# AIRZAI_LED_SENSE_FLEX_REVC.net
KiCad netlist of a schematic drawn in Altium Designer
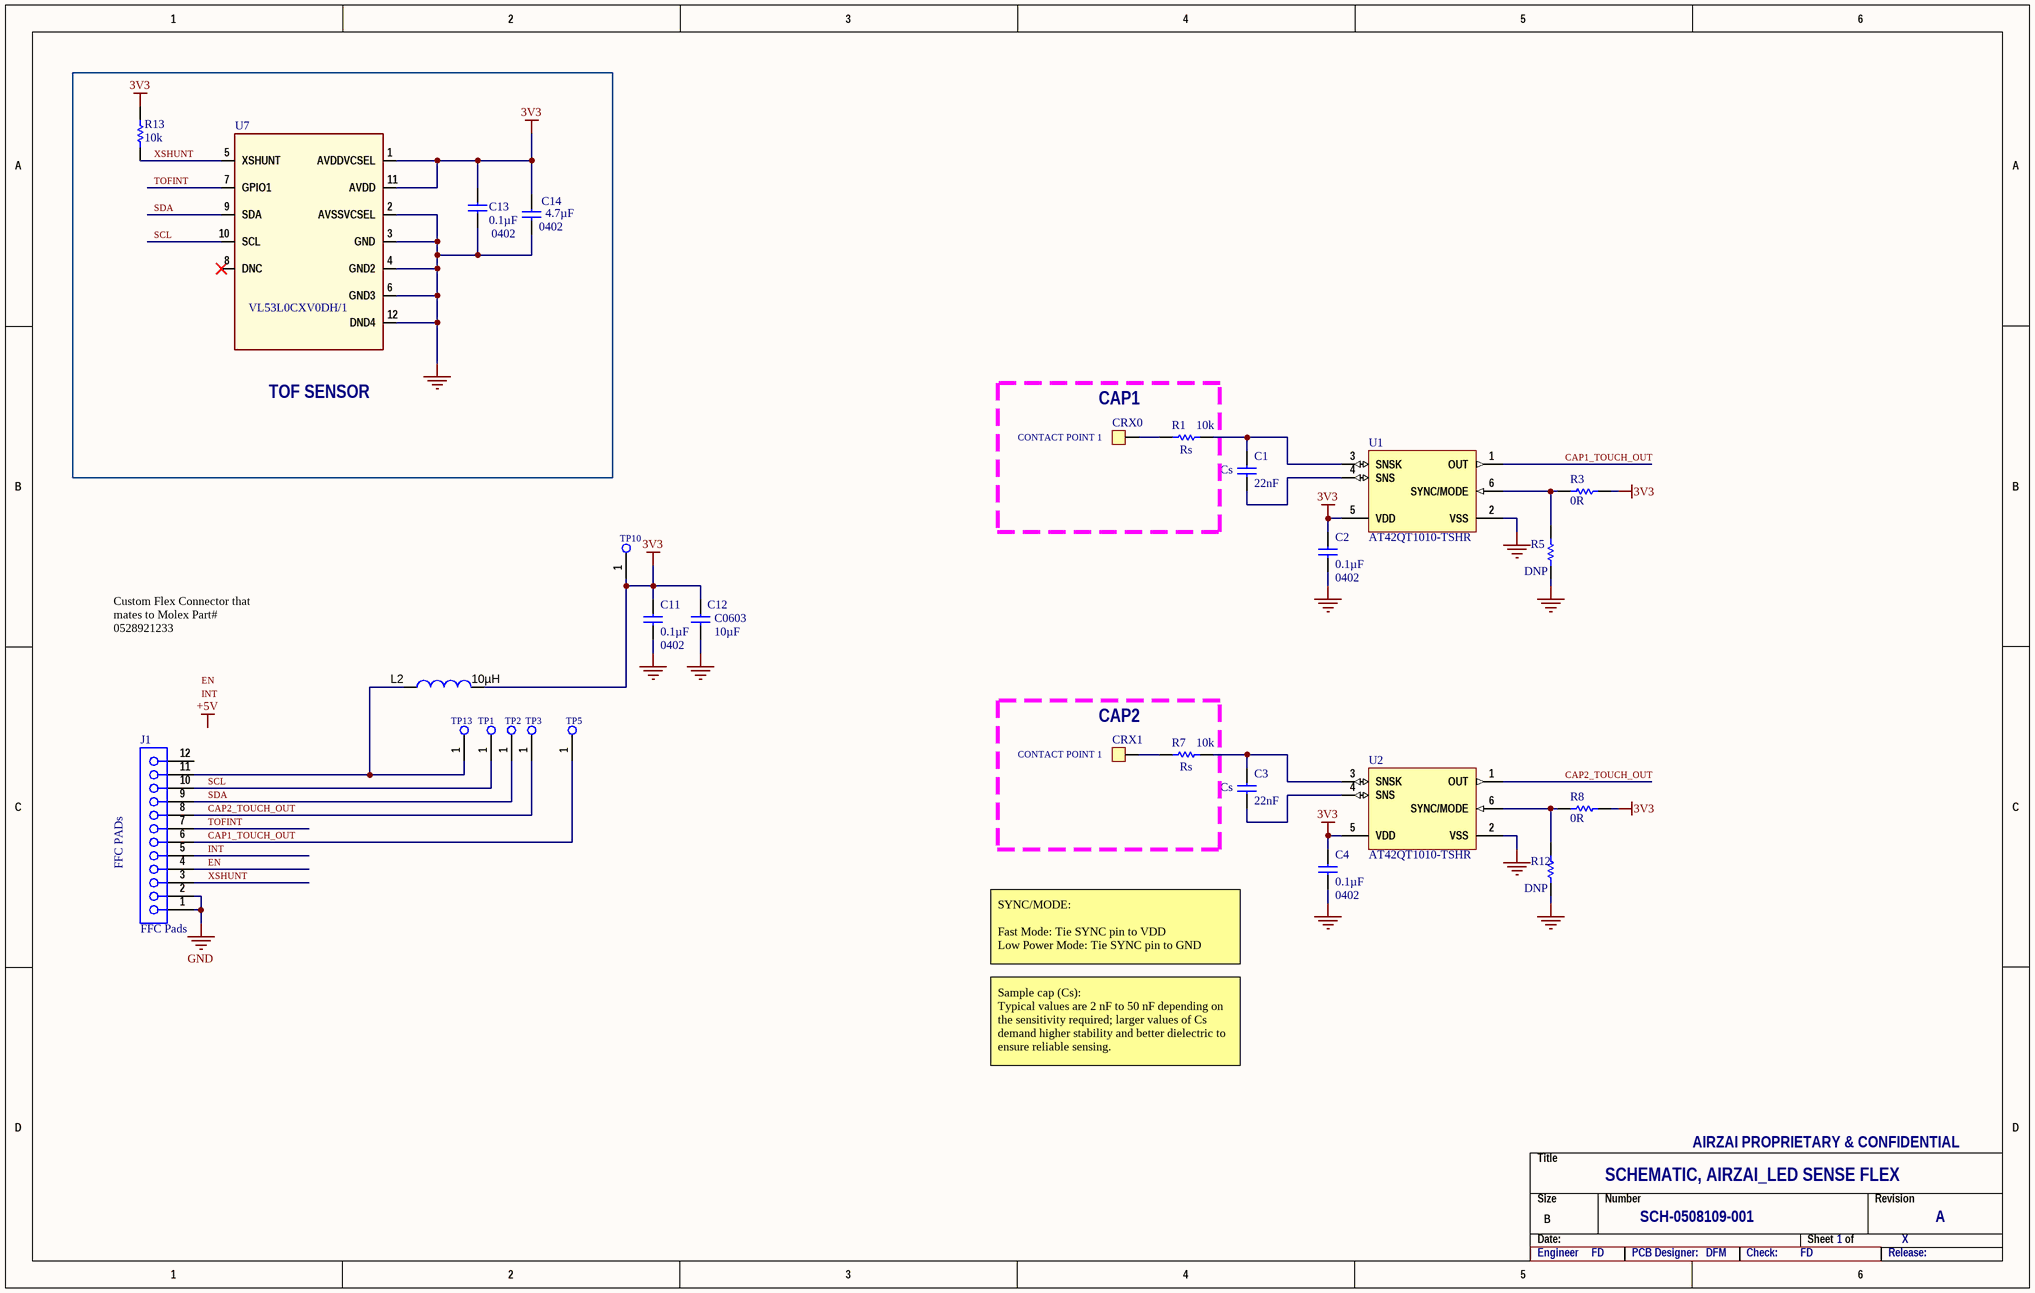
[diagram p0: AIRZAI_LED_SENSE_FLEX_REVC.SchDoc]

(export (version "E")
  (design (tool "Eeschema 10.0.6"))
  (components
    (comp (ref "C1")
      (value "22nF")
      (footprint "0402CAP")
      (description "Capacitor, X7R, ±10%")
      (fields
        (field (name "MANUFACTURER") "TDK")
        (field (name "MANUFACTURER PART NUMBER") "CGA2B2X7R1E223K050BA")
      )
      (libsource (lib "Nordic Passive DB") (part "CAP"))
    )
    (comp (ref "C2")
      (value "0.1µF")
      (footprint "0402")
      (description "Capacitor, X7R, ±10%")
      (fields (field (name "MANUFACTURER") "TDK") (field (name "MANUFACTURER PART NUMBER") "C1005X7R1C104K"))
      (libsource (lib "Nordic Passive DB") (part "CAP"))
    )
    (comp (ref "C3")
      (value "22nF")
      (footprint "0402CAP")
      (description "Capacitor, X7R, ±10%")
      (fields
        (field (name "MANUFACTURER") "TDK")
        (field (name "MANUFACTURER PART NUMBER") "CGA2B2X7R1E223K050BA")
      )
      (libsource (lib "Nordic Passive DB") (part "CAP"))
    )
    (comp (ref "C4")
      (value "0.1µF")
      (footprint "0402")
      (description "Capacitor, X7R, ±10%")
      (fields (field (name "MANUFACTURER") "TDK") (field (name "MANUFACTURER PART NUMBER") "C1005X7R1C104K"))
      (libsource (lib "Nordic Passive DB") (part "CAP"))
    )
    (comp (ref "C11")
      (value "0.1µF")
      (footprint "0402")
      (description "Capacitor, X7R, ±10%")
      (fields (field (name "MANUFACTURER") "TDK") (field (name "MANUFACTURER PART NUMBER") "C1005X7R1C104K"))
      (libsource (lib "Nordic Passive DB") (part "CAP"))
    )
    (comp (ref "C12")
      (value "10µF")
      (footprint "C0603")
      (description "Capacitor, X7R, ±10%")
      (fields
        (field (name "MANUFACTURER") "MURATA")
        (field (name "MANUFACTURER PART NUMBER") "GRM188R60J106ME47D")
      )
      (libsource (lib "Nordic Passive DB") (part "CAP"))
    )
    (comp (ref "C13")
      (value "0.1µF")
      (footprint "0402")
      (description "Capacitor, X7R, ±10%")
      (fields (field (name "MANUFACTURER") "TDK") (field (name "MANUFACTURER PART NUMBER") "C1005X7R1C104K"))
      (libsource (lib "Nordic Passive DB") (part "CAP"))
    )
    (comp (ref "C14")
      (value "4.7µF")
      (footprint "0402")
      (description "Capacitor, X7R, ±10%")
      (fields (field (name "MANUFACTURER") "TDK") (field (name "MANUFACTURER PART NUMBER") "C1005X5R0J475M"))
      (libsource (lib "Nordic Passive DB") (part "CAP"))
    )
    (comp (ref "CRX0")
      (value "CONTACT POINT 1")
      (footprint "CONTACT_POINT_1CM _SQ")
      (libsource (lib "AIRZAI_LED_SENSE_FLEX_REVA") (part "WIRE_POINT"))
    )
    (comp (ref "CRX1")
      (value "CONTACT POINT 1")
      (footprint "CONTACT_POINT_1CM _SQ")
      (libsource (lib "AIRZAI_LED_SENSE_FLEX_REVA") (part "WIRE_POINT"))
    )
    (comp (ref "J1")
      (value "FFC Pads")
      (footprint "FFC_Pads")
      (description "0.5 mm Pitch FFC Pads")
      (libsource (lib "AIRZAI_LED_SENSE_FLEX_REVA") (part "FFC_PADS"))
    )
    (comp (ref "L2")
      (value "CB2012T100KR")
      (footprint "0805")
      (description "Inductor, 10 µH, 0.5A, 0.65 ohm, SMD")
      (fields
        (field (name "MANUFACTURER") "Taiyo Yuden")
        (field (name "TOLERANCE") "10%")
        (field (name "VALUEDISPLAYED") "10µH")
      )
      (libsource (lib "AIRZAI_LED_SENSE_FLEX_REVA") (part "CB2012T100KR"))
    )
    (comp (ref "R1")
      (value "10k")
      (footprint "0402")
      (description "10k 0.063W 1% 0402 (1005 Metric)  SMD")
      (fields (field (name "TOLERANCE") "None") (field (name "POWER") "0.063W"))
      (libsource (lib "AIRZAI_LED_SENSE_FLEX_REVA") (part "RES"))
    )
    (comp (ref "R3")
      (value "0R")
      (footprint "0402")
      (description "Jumper 0402 (1005 Metric)")
      (fields (field (name "TOLERANCE") "None") (field (name "MANUFACTURER") "Panasonic"))
      (libsource (lib "AIRZAI_LED_SENSE_FLEX_REVA") (part "RES"))
    )
    (comp (ref "R5")
      (value "DNP")
      (footprint "0402")
      (fields
        (field (name "TOLERANCE") "None")
        (field (name "POWER") "0.0625 W")
        (field (name "Comment") "DNP 0402(1005)")
      )
      (libsource (lib "AIRZAI_LED_SENSE_FLEX_REVA") (part "RES"))
    )
    (comp (ref "R7")
      (value "10k")
      (footprint "0402")
      (description "10k 0.063W 1% 0402 (1005 Metric)  SMD")
      (fields (field (name "TOLERANCE") "None") (field (name "POWER") "0.063W"))
      (libsource (lib "AIRZAI_LED_SENSE_FLEX_REVA") (part "RES"))
    )
    (comp (ref "R8")
      (value "0R")
      (footprint "0402")
      (description "Jumper 0402 (1005 Metric)")
      (fields (field (name "TOLERANCE") "None") (field (name "MANUFACTURER") "Panasonic"))
      (libsource (lib "AIRZAI_LED_SENSE_FLEX_REVA") (part "RES"))
    )
    (comp (ref "R12")
      (value "DNP")
      (footprint "0402")
      (fields
        (field (name "TOLERANCE") "None")
        (field (name "POWER") "0.0625 W")
        (field (name "Comment") "DNP 0402(1005)")
      )
      (libsource (lib "AIRZAI_LED_SENSE_FLEX_REVA") (part "RES"))
    )
    (comp (ref "R13")
      (value "10k")
      (footprint "0402")
      (description "10k 0.063W 1% 0402 (1005 Metric)  SMD")
      (fields (field (name "TOLERANCE") "None") (field (name "POWER") "0.063W"))
      (libsource (lib "AIRZAI_LED_SENSE_FLEX_REVA") (part "RES"))
    )
    (comp (ref "TP1")
      (value "Test Point")
      (footprint "TP_0.9MM")
      (libsource (lib "AIRZAI_LED_SENSE_FLEX_REVA") (part "Test Point"))
    )
    (comp (ref "TP2")
      (value "Test Point")
      (footprint "TP_0.9MM")
      (libsource (lib "AIRZAI_LED_SENSE_FLEX_REVA") (part "Test Point"))
    )
    (comp (ref "TP3")
      (value "Test Point")
      (footprint "TP_0.9MM")
      (libsource (lib "AIRZAI_LED_SENSE_FLEX_REVA") (part "Test Point"))
    )
    (comp (ref "TP5")
      (value "Test Point")
      (footprint "TP_0.9MM")
      (libsource (lib "AIRZAI_LED_SENSE_FLEX_REVA") (part "Test Point"))
    )
    (comp (ref "TP10")
      (value "Test Point")
      (footprint "TP_0.9MM")
      (libsource (lib "AIRZAI_LED_SENSE_FLEX_REVA") (part "Test Point"))
    )
    (comp (ref "TP13")
      (value "Test Point")
      (footprint "TP_0.9MM")
      (libsource (lib "AIRZAI_LED_SENSE_FLEX_REVA") (part "Test Point"))
    )
    (comp (ref "U1")
      (value "AT42QT1010-TSHR")
      (footprint "SOT-23-6-AT42QT1010-TSHR")
      (description "One-channel Touch Sensor IC with Reset Timer, -40° to +85° C, 6-pin SOT23")
      (libsource (lib "AIRZAI_LED_SENSE_FLEX_REVA") (part "AT42QT1010-TSHR"))
    )
    (comp (ref "U2")
      (value "AT42QT1010-TSHR")
      (footprint "SOT-23-6-AT42QT1010-TSHR")
      (description "One-channel Touch Sensor IC with Reset Timer, -40° to +85° C, 6-pin SOT23")
      (libsource (lib "AIRZAI_LED_SENSE_FLEX_REVA") (part "AT42QT1010-TSHR"))
    )
    (comp (ref "U7")
      (value "VL53L0CXV0DH/1")
      (footprint "VL53L0X")
      (fields (field (name "MANUFACTURER") "ST") (field (name "TOLERANCE") "None"))
      (libsource (lib "DFM_JBKEGSVS_Library") (part "VL53L0X"))
    )
  )
  (nets
    (net (code "2") (name "/CAP1_TOUCH_OUT") (class "Default")
      (node (ref "J1") (pin "6") (pinfunction "6_6") (pintype "passive"))
      (node (ref "TP5") (pin "1") (pinfunction "1_1") (pintype "passive"))
      (node (ref "U1") (pin "1") (pinfunction "OUT_1") (pintype "output"))
    )
    (net (code "3") (name "/CAP2_TOUCH_OUT") (class "Default")
      (node (ref "J1") (pin "8") (pinfunction "8_8") (pintype "passive"))
      (node (ref "TP3") (pin "1") (pinfunction "1_1") (pintype "passive"))
      (node (ref "U2") (pin "1") (pinfunction "OUT_1") (pintype "output"))
    )
    (net (code "4") (name "/EN") (class "Default")
      (node (ref "J1") (pin "4") (pinfunction "4_4") (pintype "passive"))
    )
    (net (code "5") (name "/INT") (class "Default")
      (node (ref "J1") (pin "5") (pinfunction "5_5") (pintype "passive"))
    )
    (net (code "6") (name "/SCL") (class "Default")
      (node (ref "J1") (pin "10") (pinfunction "10_10") (pintype "passive"))
      (node (ref "TP1") (pin "1") (pinfunction "1_1") (pintype "passive"))
      (node (ref "U7") (pin "10") (pinfunction "SCL_10") (pintype "passive"))
    )
    (net (code "7") (name "/SDA") (class "Default")
      (node (ref "J1") (pin "9") (pinfunction "9_9") (pintype "passive"))
      (node (ref "TP2") (pin "1") (pinfunction "1_1") (pintype "passive"))
      (node (ref "U7") (pin "9") (pinfunction "SDA_9") (pintype "passive"))
    )
    (net (code "8") (name "/TOFINT") (class "Default")
      (node (ref "J1") (pin "7") (pinfunction "7_7") (pintype "passive"))
      (node (ref "U7") (pin "7") (pinfunction "GPIO1_7") (pintype "passive"))
    )
    (net (code "9") (name "/XSHUNT") (class "Default")
      (node (ref "J1") (pin "3") (pinfunction "3_3") (pintype "passive"))
      (node (ref "R13") (pin "2") (pinfunction "2_2") (pintype "passive"))
      (node (ref "U7") (pin "5") (pinfunction "XSHUNT_5") (pintype "passive"))
    )
    (net (code "10") (name "3V3") (class "Default")
      (node (ref "C11") (pin "1") (pinfunction "1_1") (pintype "passive"))
      (node (ref "C12") (pin "1") (pinfunction "1_1") (pintype "passive"))
      (node (ref "C13") (pin "1") (pinfunction "1_1") (pintype "passive"))
      (node (ref "C14") (pin "2") (pinfunction "2_2") (pintype "passive"))
      (node (ref "C2") (pin "1") (pinfunction "1_1") (pintype "passive"))
      (node (ref "C4") (pin "1") (pinfunction "1_1") (pintype "passive"))
      (node (ref "L2") (pin "2") (pinfunction "2_2") (pintype "passive"))
      (node (ref "R13") (pin "1") (pinfunction "1_1") (pintype "passive"))
      (node (ref "R3") (pin "2") (pinfunction "2_2") (pintype "passive"))
      (node (ref "R8") (pin "2") (pinfunction "2_2") (pintype "passive"))
      (node (ref "TP10") (pin "1") (pinfunction "1_1") (pintype "passive"))
      (node (ref "U1") (pin "5") (pinfunction "VDD_5") (pintype "power_in"))
      (node (ref "U2") (pin "5") (pinfunction "VDD_5") (pintype "power_in"))
      (node (ref "U7") (pin "1") (pinfunction "AVDDVCSEL_1") (pintype "passive"))
      (node (ref "U7") (pin "11") (pinfunction "AVDD_11") (pintype "passive"))
    )
    (net (code "11") (name "GND") (class "Default")
      (node (ref "C11") (pin "2") (pinfunction "2_2") (pintype "passive"))
      (node (ref "C12") (pin "2") (pinfunction "2_2") (pintype "passive"))
      (node (ref "C13") (pin "2") (pinfunction "2_2") (pintype "passive"))
      (node (ref "C14") (pin "1") (pinfunction "1_1") (pintype "passive"))
      (node (ref "C2") (pin "2") (pinfunction "2_2") (pintype "passive"))
      (node (ref "C4") (pin "2") (pinfunction "2_2") (pintype "passive"))
      (node (ref "J1") (pin "1") (pinfunction "1_1") (pintype "passive"))
      (node (ref "J1") (pin "2") (pinfunction "2_2") (pintype "passive"))
      (node (ref "R12") (pin "2") (pinfunction "2_2") (pintype "passive"))
      (node (ref "R5") (pin "2") (pinfunction "2_2") (pintype "passive"))
      (node (ref "U1") (pin "2") (pinfunction "VSS_2") (pintype "power_in"))
      (node (ref "U2") (pin "2") (pinfunction "VSS_2") (pintype "power_in"))
      (node (ref "U7") (pin "12") (pinfunction "DND4_12") (pintype "passive"))
      (node (ref "U7") (pin "2") (pinfunction "AVSSVCSEL_2") (pintype "passive"))
      (node (ref "U7") (pin "3") (pinfunction "GND_3") (pintype "passive"))
      (node (ref "U7") (pin "4") (pinfunction "GND2_4") (pintype "passive"))
      (node (ref "U7") (pin "6") (pinfunction "GND3_6") (pintype "passive"))
    )
    (net (code "12") (name "Net-(CRX0-Pad1)") (class "Default")
      (node (ref "CRX0") (pin "1") (pinfunction "1_1") (pintype "passive"))
      (node (ref "R1") (pin "2") (pinfunction "2_2") (pintype "passive"))
    )
    (net (code "13") (name "Net-(CRX1-Pad1)") (class "Default")
      (node (ref "CRX1") (pin "1") (pinfunction "1_1") (pintype "passive"))
      (node (ref "R7") (pin "2") (pinfunction "2_2") (pintype "passive"))
    )
    (net (code "14") (name "Net-(J1-Pad11)") (class "Default")
      (node (ref "J1") (pin "11") (pinfunction "11_11") (pintype "passive"))
      (node (ref "L2") (pin "1") (pinfunction "1_1") (pintype "passive"))
      (node (ref "TP13") (pin "1") (pinfunction "1_1") (pintype "passive"))
    )
    (net (code "15") (name "Net-(U1-SNS)") (class "Default")
      (node (ref "C1") (pin "2") (pinfunction "2_2") (pintype "passive"))
      (node (ref "U1") (pin "4") (pinfunction "SNS_4") (pintype "bidirectional"))
    )
    (net (code "16") (name "Net-(U1-SNSK)") (class "Default")
      (node (ref "C1") (pin "1") (pinfunction "1_1") (pintype "passive"))
      (node (ref "R1") (pin "1") (pinfunction "1_1") (pintype "passive"))
      (node (ref "U1") (pin "3") (pinfunction "SNSK_3") (pintype "bidirectional"))
    )
    (net (code "17") (name "Net-(U1-SYNC{slash}MODE)") (class "Default")
      (node (ref "R3") (pin "1") (pinfunction "1_1") (pintype "passive"))
      (node (ref "R5") (pin "1") (pinfunction "1_1") (pintype "passive"))
      (node (ref "U1") (pin "6") (pinfunction "SYNC/MODE_6") (pintype "input"))
    )
    (net (code "18") (name "Net-(U2-SNS)") (class "Default")
      (node (ref "C3") (pin "2") (pinfunction "2_2") (pintype "passive"))
      (node (ref "U2") (pin "4") (pinfunction "SNS_4") (pintype "bidirectional"))
    )
    (net (code "19") (name "Net-(U2-SNSK)") (class "Default")
      (node (ref "C3") (pin "1") (pinfunction "1_1") (pintype "passive"))
      (node (ref "R7") (pin "1") (pinfunction "1_1") (pintype "passive"))
      (node (ref "U2") (pin "3") (pinfunction "SNSK_3") (pintype "bidirectional"))
    )
    (net (code "20") (name "Net-(U2-SYNC{slash}MODE)") (class "Default")
      (node (ref "R12") (pin "1") (pinfunction "1_1") (pintype "passive"))
      (node (ref "R8") (pin "1") (pinfunction "1_1") (pintype "passive"))
      (node (ref "U2") (pin "6") (pinfunction "SYNC/MODE_6") (pintype "input"))
    )
    (net (code "21") (name "unconnected-(J1-Pad12)") (class "Default")
      (node (ref "J1") (pin "12") (pinfunction "12_12") (pintype "passive"))
    )
    (net (code "22") (name "unconnected-(U7-DNC-Pad8)") (class "Default")
      (node (ref "U7") (pin "8") (pinfunction "DNC_8") (pintype "passive+no_connect"))
    )
  )
)
